# V-00735-00.net
KiCad netlist of a schematic drawn in EAGLE
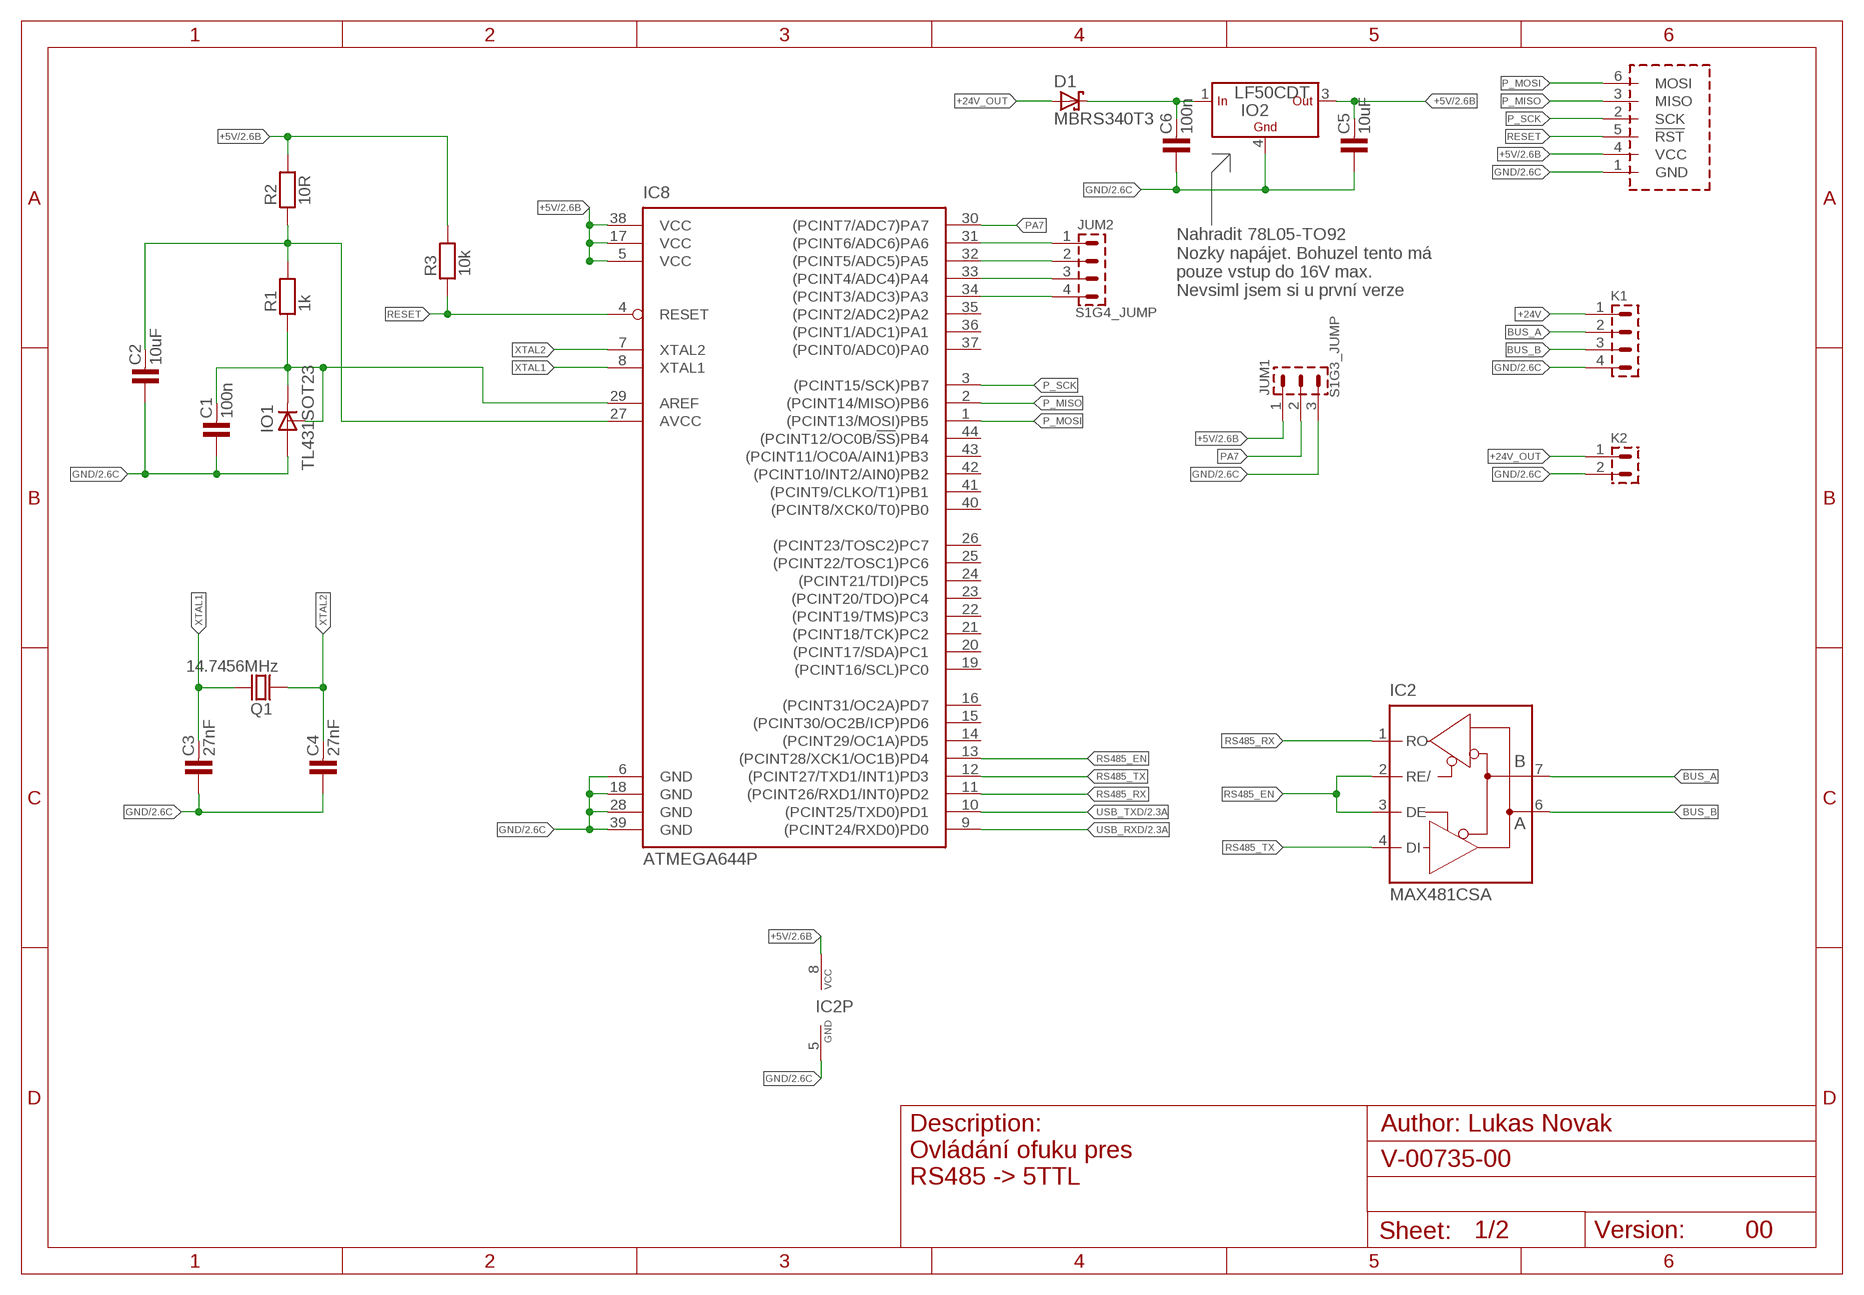
[diagram p0: schematic, sheet 1]
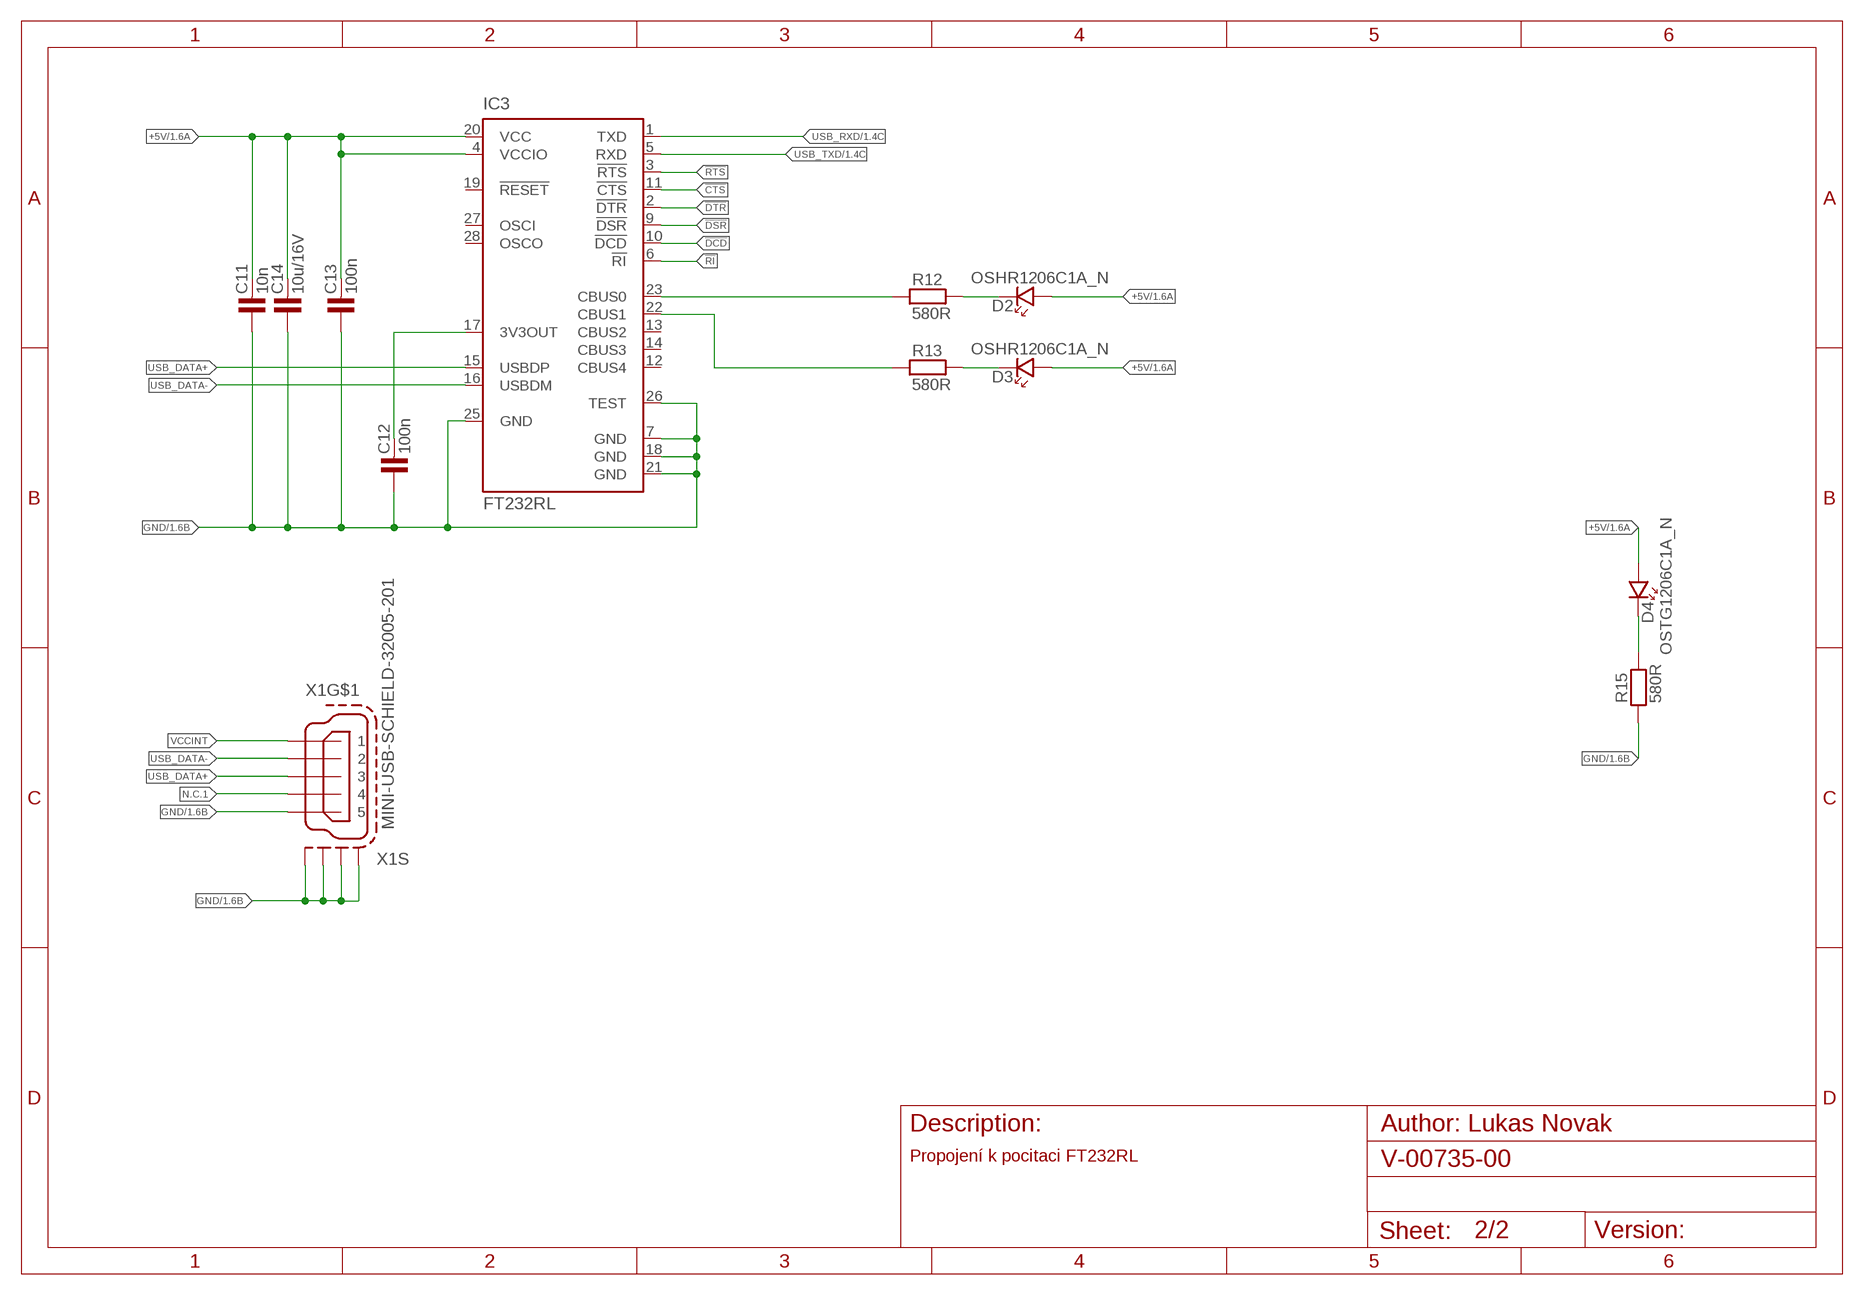
[diagram p1: schematic, sheet 2]

(export (version "E")
  (design (tool "Eeschema 10.0.6"))
  (components
    (comp (ref "C1")
      (value "100n")
      (footprint "eagle-import:1206")
      (libsource (lib "eagle-import") (part "C-KER_1206"))
    )
    (comp (ref "C2")
      (value "10uF")
      (footprint "eagle-import:1206")
      (libsource (lib "eagle-import") (part "C-KER_1206"))
    )
    (comp (ref "C3")
      (value "27nF")
      (footprint "eagle-import:0805")
      (libsource (lib "eagle-import") (part "C-KER_0805"))
    )
    (comp (ref "C4")
      (value "27nF")
      (footprint "eagle-import:0805")
      (libsource (lib "eagle-import") (part "C-KER_0805"))
    )
    (comp (ref "C5")
      (value "10uF")
      (footprint "eagle-import:1206")
      (libsource (lib "eagle-import") (part "C-KER_1206"))
    )
    (comp (ref "C6")
      (value "100n")
      (footprint "eagle-import:1206")
      (libsource (lib "eagle-import") (part "C-KER_1206"))
    )
    (comp (ref "D1")
      (value "MBRS340T3")
      (footprint "eagle-import:SMC")
      (libsource (lib "eagle-import") (part "MBRS30T34"))
    )
    (comp (ref "IC2")
      (value "MAX481CSA")
      (footprint "eagle-import:SO08")
      (fields (field (name "MF") "MAXIM"))
      (libsource (lib "eagle-import") (part "MAX481CSA"))
    )
    (comp (ref "IC8")
      (value "ATMEGA644P")
      (footprint "eagle-import:TQFP44")
      (libsource (lib "eagle-import") (part "ATMEGA644P"))
    )
    (comp (ref "IO1")
      (value "TL431SOT23")
      (footprint "eagle-import:SOT23")
      (fields (field (name "MPN") "TL431BFDT"))
      (libsource (lib "eagle-import") (part "TL431SOT23"))
    )
    (comp (ref "IO2")
      (value "LF50CDT")
      (footprint "eagle-import:DPAK")
      (libsource (lib "eagle-import") (part "LF_CDT"))
    )
    (comp (ref "JUM1")
      (value "S1G3_JUMP")
      (footprint "eagle-import:S1G3_JUM")
      (libsource (lib "eagle-import") (part "S1G3_JUMP"))
    )
    (comp (ref "JUM2")
      (value "S1G4_JUMP")
      (footprint "eagle-import:S1G4_JUM")
      (libsource (lib "eagle-import") (part "S1G4_JUMP"))
    )
    (comp (ref "K1")
      (value "PSH02-04P")
      (footprint "eagle-import:PSH02-04P")
      (libsource (lib "eagle-import") (part "PSH02-04P"))
    )
    (comp (ref "K2")
      (value "PSH02-02P")
      (footprint "eagle-import:PSH02-02P")
      (libsource (lib "eagle-import") (part "PSH02-02P"))
    )
    (comp (ref "Q1")
      (value "14.7456MHz")
      (footprint "eagle-import:HC-49U")
      (libsource (lib "eagle-import") (part "Q_HC-49U"))
    )
    (comp (ref "R1")
      (value "1k")
      (footprint "eagle-import:1206")
      (libsource (lib "eagle-import") (part "R_1206"))
    )
    (comp (ref "R2")
      (value "10R")
      (footprint "eagle-import:1206")
      (libsource (lib "eagle-import") (part "R_1206"))
    )
    (comp (ref "R3")
      (value "10k")
      (footprint "eagle-import:1206")
      (libsource (lib "eagle-import") (part "R_1206"))
    )
    (comp (ref "U$1")
      (value "AVR_PROG_SPI")
      (footprint "eagle-import:PSH02-06P")
      (libsource (lib "eagle-import") (part "AVR_PROG_SPI"))
    )
    (comp (ref "C11")
      (value "10n")
      (footprint "eagle-import:1206")
      (libsource (lib "eagle-import") (part "C-KER_1206"))
    )
    (comp (ref "C12")
      (value "100n")
      (footprint "eagle-import:1206")
      (libsource (lib "eagle-import") (part "C-KER_1206"))
    )
    (comp (ref "C13")
      (value "100n")
      (footprint "eagle-import:1206")
      (libsource (lib "eagle-import") (part "C-KER_1206"))
    )
    (comp (ref "C14")
      (value "10u/16V")
      (footprint "eagle-import:1206")
      (libsource (lib "eagle-import") (part "C-KER_1206"))
    )
    (comp (ref "D2")
      (value "OSHR1206C1A_N")
      (footprint "eagle-import:P1206")
      (libsource (lib "eagle-import") (part "LED_1206"))
    )
    (comp (ref "D3")
      (value "OSHR1206C1A_N")
      (footprint "eagle-import:P1206")
      (libsource (lib "eagle-import") (part "LED_1206"))
    )
    (comp (ref "D4")
      (value "OSTG1206C1A_N")
      (footprint "eagle-import:P1206")
      (libsource (lib "eagle-import") (part "LED_1206"))
    )
    (comp (ref "IC3")
      (value "FT232RL")
      (footprint "eagle-import:SSOP28")
      (libsource (lib "eagle-import") (part "FT232RL"))
    )
    (comp (ref "R12")
      (value "580R")
      (footprint "eagle-import:1206")
      (libsource (lib "eagle-import") (part "R_1206"))
    )
    (comp (ref "R13")
      (value "580R")
      (footprint "eagle-import:1206")
      (libsource (lib "eagle-import") (part "R_1206"))
    )
    (comp (ref "R15")
      (value "580R")
      (footprint "eagle-import:1206")
      (libsource (lib "eagle-import") (part "R_1206"))
    )
    (comp (ref "X1")
      (value "MINI-USB-SCHIELD-32005-201")
      (footprint "eagle-import:32005-201")
      (libsource (lib "eagle-import") (part "MINI-USB-SCHIELD-32005-201"))
    )
  )
  (nets
    (net (code "1") (name "+5V") (class "Default")
      (node (ref "C11") (pin "2") (pinfunction "2_2") (pintype "passive"))
      (node (ref "C13") (pin "2") (pinfunction "2_2") (pintype "passive"))
      (node (ref "C14") (pin "2") (pinfunction "2_2") (pintype "passive"))
      (node (ref "C5") (pin "2") (pinfunction "2_2") (pintype "passive"))
      (node (ref "D2") (pin "A") (pinfunction "A_A") (pintype "passive"))
      (node (ref "D3") (pin "A") (pinfunction "A_A") (pintype "passive"))
      (node (ref "D4") (pin "A") (pinfunction "A_A") (pintype "passive"))
      (node (ref "IC2") (pin "8") (pinfunction "VCC_8") (pintype "power_in"))
      (node (ref "IC3") (pin "20") (pinfunction "VCC_20") (pintype "power_in"))
      (node (ref "IC3") (pin "4") (pinfunction "VCCIO_4") (pintype "power_in"))
      (node (ref "IC8") (pin "17") (pinfunction "VCC_17") (pintype "power_in"))
      (node (ref "IC8") (pin "38") (pinfunction "VCC_38") (pintype "power_in"))
      (node (ref "IC8") (pin "5") (pinfunction "VCC_5") (pintype "power_in"))
      (node (ref "IO2") (pin "3") (pinfunction "OUT_3") (pintype "passive"))
      (node (ref "JUM1") (pin "1") (pinfunction "1_1") (pintype "passive"))
      (node (ref "R2") (pin "2") (pinfunction "2_2") (pintype "passive"))
      (node (ref "R3") (pin "2") (pinfunction "2_2") (pintype "passive"))
      (node (ref "U$1") (pin "4") (pinfunction "VCC_4") (pintype "bidirectional"))
    )
    (net (code "2") (name "+24V") (class "Default")
      (node (ref "C6") (pin "2") (pinfunction "2_2") (pintype "passive"))
      (node (ref "D1") (pin "C") (pinfunction "C_C") (pintype "passive"))
      (node (ref "IO2") (pin "1") (pinfunction "IN_1") (pintype "passive"))
      (node (ref "K1") (pin "1") (pinfunction "1_1") (pintype "passive"))
    )
    (net (code "3") (name "+24V_OUT") (class "Default")
      (node (ref "D1") (pin "A") (pinfunction "A_A") (pintype "passive"))
      (node (ref "K2") (pin "1") (pinfunction "1_1") (pintype "passive"))
    )
    (net (code "4") (name "BUS_A") (class "Default")
      (node (ref "IC2") (pin "7") (pinfunction "B_7") (pintype "passive"))
      (node (ref "K1") (pin "2") (pinfunction "2_2") (pintype "passive"))
    )
    (net (code "5") (name "BUS_B") (class "Default")
      (node (ref "IC2") (pin "6") (pinfunction "A_6") (pintype "passive"))
      (node (ref "K1") (pin "3") (pinfunction "3_3") (pintype "passive"))
    )
    (net (code "6") (name "GND") (class "Default")
      (node (ref "C1") (pin "1") (pinfunction "1_1") (pintype "passive"))
      (node (ref "C11") (pin "1") (pinfunction "1_1") (pintype "passive"))
      (node (ref "C12") (pin "1") (pinfunction "1_1") (pintype "passive"))
      (node (ref "C13") (pin "1") (pinfunction "1_1") (pintype "passive"))
      (node (ref "C14") (pin "1") (pinfunction "1_1") (pintype "passive"))
      (node (ref "C2") (pin "1") (pinfunction "1_1") (pintype "passive"))
      (node (ref "C3") (pin "1") (pinfunction "1_1") (pintype "passive"))
      (node (ref "C4") (pin "1") (pinfunction "1_1") (pintype "passive"))
      (node (ref "C5") (pin "1") (pinfunction "1_1") (pintype "passive"))
      (node (ref "C6") (pin "1") (pinfunction "1_1") (pintype "passive"))
      (node (ref "IC2") (pin "5") (pinfunction "GND_5") (pintype "power_in"))
      (node (ref "IC3") (pin "18") (pinfunction "GND_18") (pintype "power_in"))
      (node (ref "IC3") (pin "21") (pinfunction "GND_21") (pintype "power_in"))
      (node (ref "IC3") (pin "25") (pinfunction "GND_25") (pintype "power_in"))
      (node (ref "IC3") (pin "26") (pinfunction "TEST_26") (pintype "input"))
      (node (ref "IC3") (pin "7") (pinfunction "GND_7") (pintype "power_in"))
      (node (ref "IC8") (pin "18") (pinfunction "GND_18") (pintype "power_in"))
      (node (ref "IC8") (pin "28") (pinfunction "GND_28") (pintype "power_in"))
      (node (ref "IC8") (pin "39") (pinfunction "GND_39") (pintype "power_in"))
      (node (ref "IC8") (pin "6") (pinfunction "GND_6") (pintype "power_in"))
      (node (ref "IO1") (pin "3") (pinfunction "A_3") (pintype "bidirectional"))
      (node (ref "IO2") (pin "4") (pinfunction "GND_4") (pintype "passive"))
      (node (ref "JUM1") (pin "3") (pinfunction "3_3") (pintype "passive"))
      (node (ref "K1") (pin "4") (pinfunction "4_4") (pintype "passive"))
      (node (ref "K2") (pin "2") (pinfunction "2_2") (pintype "passive"))
      (node (ref "R15") (pin "1") (pinfunction "1_1") (pintype "passive"))
      (node (ref "U$1") (pin "1") (pinfunction "GND_1") (pintype "bidirectional"))
      (node (ref "X1") (pin "5") (pinfunction "5_5") (pintype "passive"))
      (node (ref "X1") (pin "M1") (pinfunction "S1_M1") (pintype "passive"))
      (node (ref "X1") (pin "M2") (pinfunction "S2_M2") (pintype "passive"))
      (node (ref "X1") (pin "M3") (pinfunction "S3_M3") (pintype "passive"))
      (node (ref "X1") (pin "M4") (pinfunction "S4_M4") (pintype "passive"))
    )
    (net (code "7") (name "N.C.1") (class "Default")
      (node (ref "X1") (pin "4") (pinfunction "4_4") (pintype "passive"))
    )
    (net (code "8") (name "Net-(D2-PadK)") (class "Default")
      (node (ref "D2") (pin "K") (pinfunction "K_K") (pintype "passive"))
      (node (ref "R12") (pin "2") (pinfunction "2_2") (pintype "passive"))
    )
    (net (code "9") (name "Net-(D3-PadK)") (class "Default")
      (node (ref "D3") (pin "K") (pinfunction "K_K") (pintype "passive"))
      (node (ref "R13") (pin "2") (pinfunction "2_2") (pintype "passive"))
    )
    (net (code "10") (name "Net-(D4-PadK)") (class "Default")
      (node (ref "D4") (pin "K") (pinfunction "K_K") (pintype "passive"))
      (node (ref "R15") (pin "2") (pinfunction "2_2") (pintype "passive"))
    )
    (net (code "11") (name "Net-(IC3-3V3OUT)") (class "Default")
      (node (ref "C12") (pin "2") (pinfunction "2_2") (pintype "passive"))
      (node (ref "IC3") (pin "17") (pinfunction "3V3OUT_17") (pintype "output"))
    )
    (net (code "12") (name "Net-(IC3-CBUS0)") (class "Default")
      (node (ref "IC3") (pin "23") (pinfunction "CBUS0_23") (pintype "bidirectional"))
      (node (ref "R12") (pin "1") (pinfunction "1_1") (pintype "passive"))
    )
    (net (code "13") (name "Net-(IC3-CBUS1)") (class "Default")
      (node (ref "IC3") (pin "22") (pinfunction "CBUS1_22") (pintype "bidirectional"))
      (node (ref "R13") (pin "1") (pinfunction "1_1") (pintype "passive"))
    )
    (net (code "14") (name "Net-(IC8-(PCINT3{slash}ADC3)PA3)") (class "Default")
      (node (ref "IC8") (pin "34") (pinfunction "(PCINT3/ADC3)PA3_34") (pintype "bidirectional"))
      (node (ref "JUM2") (pin "4") (pinfunction "4_4") (pintype "passive"))
    )
    (net (code "15") (name "Net-(IC8-(PCINT4{slash}ADC4)PA4)") (class "Default")
      (node (ref "IC8") (pin "33") (pinfunction "(PCINT4/ADC4)PA4_33") (pintype "bidirectional"))
      (node (ref "JUM2") (pin "3") (pinfunction "3_3") (pintype "passive"))
    )
    (net (code "16") (name "Net-(IC8-(PCINT5{slash}ADC5)PA5)") (class "Default")
      (node (ref "IC8") (pin "32") (pinfunction "(PCINT5/ADC5)PA5_32") (pintype "bidirectional"))
      (node (ref "JUM2") (pin "2") (pinfunction "2_2") (pintype "passive"))
    )
    (net (code "17") (name "Net-(IC8-(PCINT6{slash}ADC6)PA6)") (class "Default")
      (node (ref "IC8") (pin "31") (pinfunction "(PCINT6/ADC6)PA6_31") (pintype "bidirectional"))
      (node (ref "JUM2") (pin "1") (pinfunction "1_1") (pintype "passive"))
    )
    (net (code "18") (name "Net-(IC8-AREF)") (class "Default")
      (node (ref "C1") (pin "2") (pinfunction "2_2") (pintype "passive"))
      (node (ref "IC8") (pin "29") (pinfunction "AREF_29") (pintype "passive"))
      (node (ref "IO1") (pin "1") (pinfunction "C_1") (pintype "bidirectional"))
      (node (ref "IO1") (pin "2") (pinfunction "R_2") (pintype "bidirectional"))
      (node (ref "R1") (pin "1") (pinfunction "1_1") (pintype "passive"))
    )
    (net (code "19") (name "Net-(IC8-AVCC)") (class "Default")
      (node (ref "C2") (pin "2") (pinfunction "2_2") (pintype "passive"))
      (node (ref "IC8") (pin "27") (pinfunction "AVCC_27") (pintype "power_in"))
      (node (ref "R1") (pin "2") (pinfunction "2_2") (pintype "passive"))
      (node (ref "R2") (pin "1") (pinfunction "1_1") (pintype "passive"))
    )
    (net (code "20") (name "PA7") (class "Default")
      (node (ref "IC8") (pin "30") (pinfunction "(PCINT7/ADC7)PA7_30") (pintype "bidirectional"))
      (node (ref "JUM1") (pin "2") (pinfunction "2_2") (pintype "passive"))
    )
    (net (code "21") (name "P_MISO") (class "Default")
      (node (ref "IC8") (pin "2") (pinfunction "(PCINT14/MISO)PB6_2") (pintype "bidirectional"))
      (node (ref "U$1") (pin "3") (pinfunction "MISO_3") (pintype "bidirectional"))
    )
    (net (code "22") (name "P_MOSI") (class "Default")
      (node (ref "IC8") (pin "1") (pinfunction "(PCINT13/MOSI)PB5_1") (pintype "bidirectional"))
      (node (ref "U$1") (pin "6") (pinfunction "MOSI_6") (pintype "bidirectional"))
    )
    (net (code "23") (name "P_SCK") (class "Default")
      (node (ref "IC8") (pin "3") (pinfunction "(PCINT15/SCK)PB7_3") (pintype "bidirectional"))
      (node (ref "U$1") (pin "2") (pinfunction "SCK_2") (pintype "bidirectional"))
    )
    (net (code "24") (name "RESET") (class "Default")
      (node (ref "IC8") (pin "4") (pinfunction "RESET_4") (pintype "input"))
      (node (ref "R3") (pin "1") (pinfunction "1_1") (pintype "passive"))
      (node (ref "U$1") (pin "5") (pinfunction "~{RST}_5") (pintype "bidirectional"))
    )
    (net (code "25") (name "RS485_EN") (class "Default")
      (node (ref "IC2") (pin "2") (pinfunction "RE/_2") (pintype "input"))
      (node (ref "IC2") (pin "3") (pinfunction "DE_3") (pintype "input"))
      (node (ref "IC8") (pin "13") (pinfunction "(PCINT28/XCK1/OC1B)PD4_13") (pintype "bidirectional"))
    )
    (net (code "26") (name "RS485_RX") (class "Default")
      (node (ref "IC2") (pin "1") (pinfunction "RO_1") (pintype "output"))
      (node (ref "IC8") (pin "11") (pinfunction "(PCINT26/RXD1/INT0)PD2_11") (pintype "bidirectional"))
    )
    (net (code "27") (name "RS485_TX") (class "Default")
      (node (ref "IC2") (pin "4") (pinfunction "DI_4") (pintype "input"))
      (node (ref "IC8") (pin "12") (pinfunction "(PCINT27/TXD1/INT1)PD3_12") (pintype "bidirectional"))
    )
    (net (code "28") (name "USB_DATA+") (class "Default")
      (node (ref "IC3") (pin "15") (pinfunction "USBDP_15") (pintype "bidirectional"))
      (node (ref "X1") (pin "3") (pinfunction "3_3") (pintype "passive"))
    )
    (net (code "29") (name "USB_DATA-") (class "Default")
      (node (ref "IC3") (pin "16") (pinfunction "USBDM_16") (pintype "bidirectional"))
      (node (ref "X1") (pin "2") (pinfunction "2_2") (pintype "passive"))
    )
    (net (code "30") (name "USB_RXD") (class "Default")
      (node (ref "IC3") (pin "1") (pinfunction "TXD_1") (pintype "output"))
      (node (ref "IC8") (pin "9") (pinfunction "(PCINT24/RXD0)PD0_9") (pintype "bidirectional"))
    )
    (net (code "31") (name "USB_TXD") (class "Default")
      (node (ref "IC3") (pin "5") (pinfunction "RXD_5") (pintype "input"))
      (node (ref "IC8") (pin "10") (pinfunction "(PCINT25/TXD0)PD1_10") (pintype "bidirectional"))
    )
    (net (code "32") (name "VCCINT") (class "Default")
      (node (ref "X1") (pin "1") (pinfunction "1_1") (pintype "passive"))
    )
    (net (code "33") (name "XTAL1") (class "Default")
      (node (ref "C3") (pin "2") (pinfunction "2_2") (pintype "passive"))
      (node (ref "IC8") (pin "8") (pinfunction "XTAL1_8") (pintype "bidirectional"))
      (node (ref "Q1") (pin "2") (pinfunction "2_2") (pintype "passive"))
    )
    (net (code "34") (name "XTAL2") (class "Default")
      (node (ref "C4") (pin "2") (pinfunction "2_2") (pintype "passive"))
      (node (ref "IC8") (pin "7") (pinfunction "XTAL2_7") (pintype "bidirectional"))
      (node (ref "Q1") (pin "1") (pinfunction "1_1") (pintype "passive"))
    )
    (net (code "35") (name "unconnected-(IC3-CBUS2-Pad13)") (class "Default")
      (node (ref "IC3") (pin "13") (pinfunction "CBUS2_13") (pintype "bidirectional"))
    )
    (net (code "36") (name "unconnected-(IC3-CBUS3-Pad14)") (class "Default")
      (node (ref "IC3") (pin "14") (pinfunction "CBUS3_14") (pintype "bidirectional"))
    )
    (net (code "37") (name "unconnected-(IC3-CBUS4-Pad12)") (class "Default")
      (node (ref "IC3") (pin "12") (pinfunction "CBUS4_12") (pintype "bidirectional"))
    )
    (net (code "38") (name "unconnected-(IC3-OSCI-Pad27)") (class "Default")
      (node (ref "IC3") (pin "27") (pinfunction "OSCI_27") (pintype "input"))
    )
    (net (code "39") (name "unconnected-(IC3-OSCO-Pad28)") (class "Default")
      (node (ref "IC3") (pin "28") (pinfunction "OSCO_28") (pintype "output"))
    )
    (net (code "40") (name "unconnected-(IC3-~{RESET}-Pad19)") (class "Default")
      (node (ref "IC3") (pin "19") (pinfunction "~{RESET}_19") (pintype "input"))
    )
    (net (code "41") (name "unconnected-(IC8-(PCINT0{slash}ADC0)PA0-Pad37)") (class "Default")
      (node (ref "IC8") (pin "37") (pinfunction "(PCINT0/ADC0)PA0_37") (pintype "bidirectional"))
    )
    (net (code "42") (name "unconnected-(IC8-(PCINT1{slash}ADC1)PA1-Pad36)") (class "Default")
      (node (ref "IC8") (pin "36") (pinfunction "(PCINT1/ADC1)PA1_36") (pintype "bidirectional"))
    )
    (net (code "43") (name "unconnected-(IC8-(PCINT2{slash}ADC2)PA2-Pad35)") (class "Default")
      (node (ref "IC8") (pin "35") (pinfunction "(PCINT2/ADC2)PA2_35") (pintype "bidirectional"))
    )
    (net (code "44") (name "unconnected-(IC8-(PCINT8{slash}XCK0{slash}T0)PB0-Pad40)") (class "Default")
      (node (ref "IC8") (pin "40") (pinfunction "(PCINT8/XCK0/T0)PB0_40") (pintype "bidirectional"))
    )
    (net (code "45") (name "unconnected-(IC8-(PCINT9{slash}CLKO{slash}T1)PB1-Pad41)") (class "Default")
      (node (ref "IC8") (pin "41") (pinfunction "(PCINT9/CLKO/T1)PB1_41") (pintype "bidirectional"))
    )
    (net (code "46") (name "unconnected-(IC8-(PCINT10{slash}INT2{slash}AIN0)PB2-Pad42)") (class "Default")
      (node (ref "IC8") (pin "42") (pinfunction "(PCINT10/INT2/AIN0)PB2_42") (pintype "bidirectional"))
    )
    (net (code "47") (name "unconnected-(IC8-(PCINT11{slash}OC0A{slash}AIN1)PB3-Pad43)") (class "Default")
      (node (ref "IC8") (pin "43") (pinfunction "(PCINT11/OC0A/AIN1)PB3_43") (pintype "bidirectional"))
    )
    (net (code "48") (name "unconnected-(IC8-(PCINT12{slash}OC0B{slash}~{SS})PB4-Pad44)") (class "Default")
      (node (ref "IC8") (pin "44") (pinfunction "(PCINT12/OC0B/~{SS})PB4_44") (pintype "bidirectional"))
    )
    (net (code "49") (name "unconnected-(IC8-(PCINT16{slash}SCL)PC0-Pad19)") (class "Default")
      (node (ref "IC8") (pin "19") (pinfunction "(PCINT16/SCL)PC0_19") (pintype "output"))
    )
    (net (code "50") (name "unconnected-(IC8-(PCINT17{slash}SDA)PC1-Pad20)") (class "Default")
      (node (ref "IC8") (pin "20") (pinfunction "(PCINT17/SDA)PC1_20") (pintype "output"))
    )
    (net (code "51") (name "unconnected-(IC8-(PCINT18{slash}TCK)PC2-Pad21)") (class "Default")
      (node (ref "IC8") (pin "21") (pinfunction "(PCINT18/TCK)PC2_21") (pintype "output"))
    )
    (net (code "52") (name "unconnected-(IC8-(PCINT19{slash}TMS)PC3-Pad22)") (class "Default")
      (node (ref "IC8") (pin "22") (pinfunction "(PCINT19/TMS)PC3_22") (pintype "output"))
    )
    (net (code "53") (name "unconnected-(IC8-(PCINT20{slash}TDO)PC4-Pad23)") (class "Default")
      (node (ref "IC8") (pin "23") (pinfunction "(PCINT20/TDO)PC4_23") (pintype "output"))
    )
    (net (code "54") (name "unconnected-(IC8-(PCINT21{slash}TDI)PC5-Pad24)") (class "Default")
      (node (ref "IC8") (pin "24") (pinfunction "(PCINT21/TDI)PC5_24") (pintype "output"))
    )
    (net (code "55") (name "unconnected-(IC8-(PCINT22{slash}TOSC1)PC6-Pad25)") (class "Default")
      (node (ref "IC8") (pin "25") (pinfunction "(PCINT22/TOSC1)PC6_25") (pintype "output"))
    )
    (net (code "56") (name "unconnected-(IC8-(PCINT23{slash}TOSC2)PC7-Pad26)") (class "Default")
      (node (ref "IC8") (pin "26") (pinfunction "(PCINT23/TOSC2)PC7_26") (pintype "output"))
    )
    (net (code "57") (name "unconnected-(IC8-(PCINT29{slash}OC1A)PD5-Pad14)") (class "Default")
      (node (ref "IC8") (pin "14") (pinfunction "(PCINT29/OC1A)PD5_14") (pintype "bidirectional"))
    )
    (net (code "58") (name "unconnected-(IC8-(PCINT30{slash}OC2B{slash}ICP)PD6-Pad15)") (class "Default")
      (node (ref "IC8") (pin "15") (pinfunction "(PCINT30/OC2B/ICP)PD6_15") (pintype "bidirectional"))
    )
    (net (code "59") (name "unconnected-(IC8-(PCINT31{slash}OC2A)PD7-Pad16)") (class "Default")
      (node (ref "IC8") (pin "16") (pinfunction "(PCINT31/OC2A)PD7_16") (pintype "bidirectional"))
    )
    (net (code "60") (name "~{CTS}") (class "Default")
      (node (ref "IC3") (pin "11") (pinfunction "~{CTS}_11") (pintype "input"))
    )
    (net (code "61") (name "~{DCD}") (class "Default")
      (node (ref "IC3") (pin "10") (pinfunction "~{DCD}_10") (pintype "input"))
    )
    (net (code "62") (name "~{DSR}") (class "Default")
      (node (ref "IC3") (pin "9") (pinfunction "~{DSR}_9") (pintype "input"))
    )
    (net (code "63") (name "~{DTR}") (class "Default")
      (node (ref "IC3") (pin "2") (pinfunction "~{DTR}_2") (pintype "output"))
    )
    (net (code "64") (name "~{RI}") (class "Default")
      (node (ref "IC3") (pin "6") (pinfunction "~{RI}_6") (pintype "input"))
    )
    (net (code "65") (name "~{RTS}") (class "Default")
      (node (ref "IC3") (pin "3") (pinfunction "~{RTS}_3") (pintype "output"))
    )
  )
)
